# Inverter.net
KiCad netlist of a schematic drawn in Altium Designer
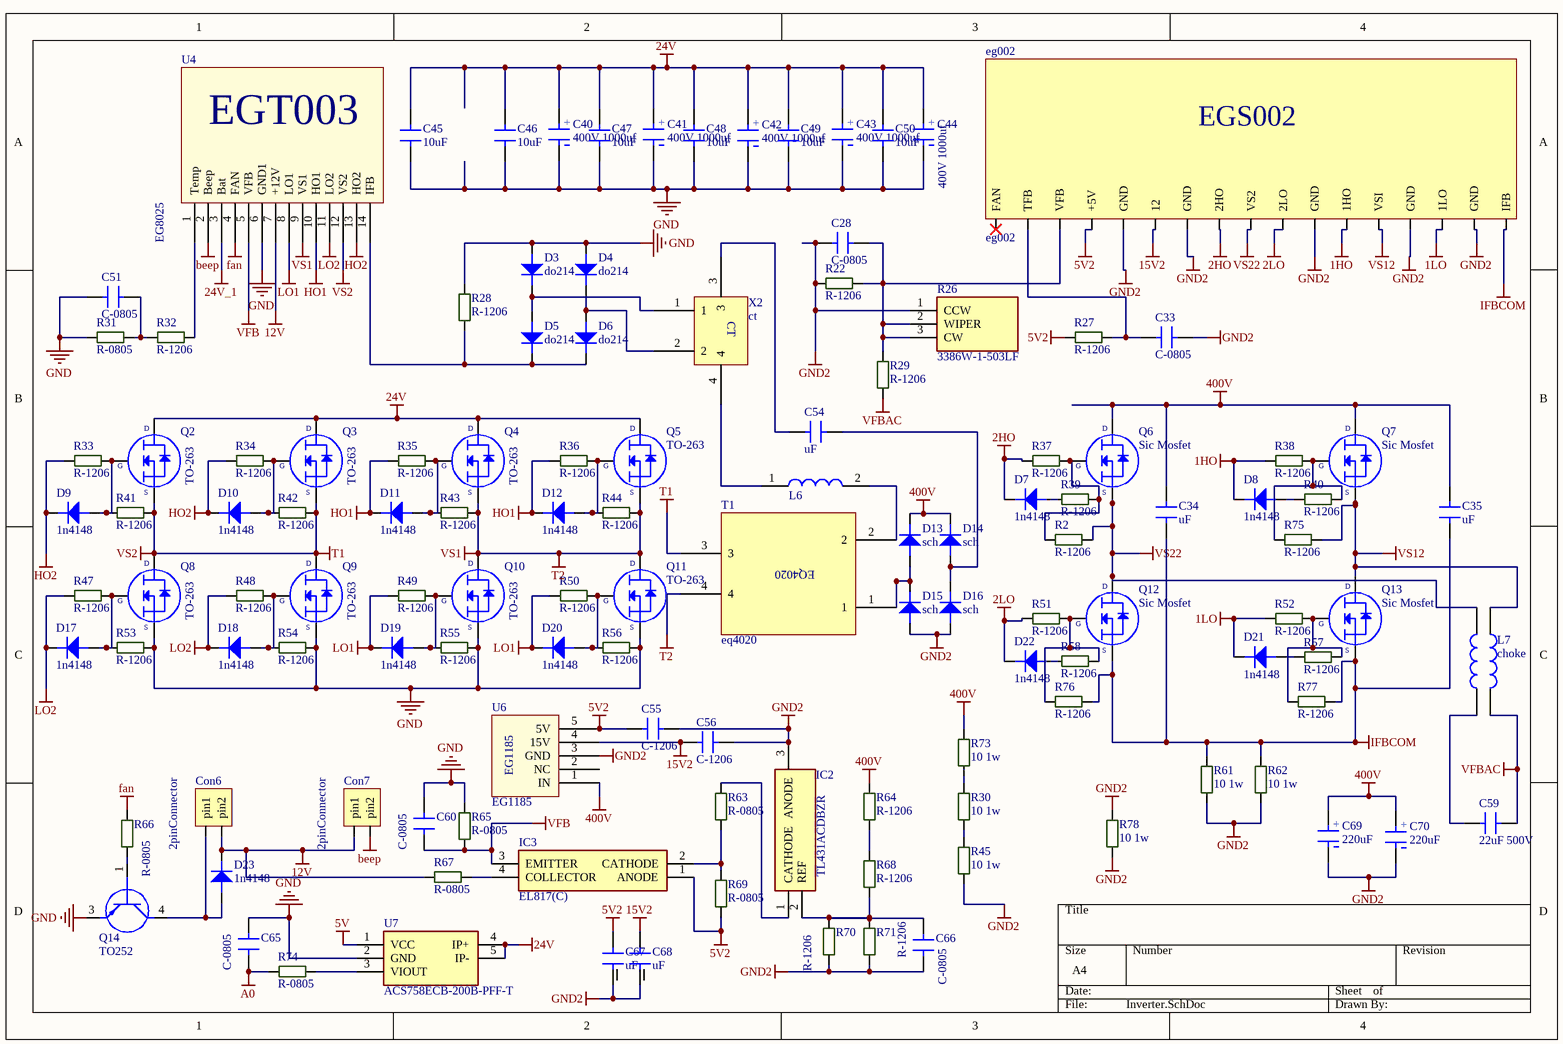
[diagram p0: Inverter.SchDoc]

(export (version "E")
  (design (tool "Eeschema 10.0.6"))
  (components
    (comp (ref "C28") (value "C-0805") (footprint "C-0805W") (libsource (lib "Schlib1") (part "C-0805")))
    (comp (ref "C33") (value "C-0805") (footprint "C-0805W") (libsource (lib "Schlib1") (part "C-0805")))
    (comp (ref "C34") (value "uF") (footprint "680nF bulk") (libsource (lib "Schlib1") (part "680")))
    (comp (ref "C35") (value "uF") (footprint "680nF bulk") (libsource (lib "Schlib1") (part "680")))
    (comp (ref "C40")
      (value "400V 1000uf")
      (footprint "CAP_EEETC1C331V")
      (fields
        (field (name "MANUFACTURER") "Nichicon")
        (field (name "MANUFACTURER PART NUMBER") "LKS1J472MESZ")
        (field (name "TOLERANCE") "20%")
      )
      (libsource (lib "Schlib1") (part "Aluminum Electrolytic Capacitors"))
    )
    (comp (ref "C41")
      (value "400V 1000uf")
      (footprint "CAP_EEETC1C331V")
      (fields
        (field (name "MANUFACTURER") "Nichicon")
        (field (name "MANUFACTURER PART NUMBER") "LKS1J472MESZ")
        (field (name "TOLERANCE") "20%")
      )
      (libsource (lib "Schlib1") (part "Aluminum Electrolytic Capacitors"))
    )
    (comp (ref "C42")
      (value "400V 1000uf")
      (footprint "CAP_EEETC1C331V")
      (fields
        (field (name "MANUFACTURER") "Nichicon")
        (field (name "MANUFACTURER PART NUMBER") "LKS1J472MESZ")
        (field (name "TOLERANCE") "20%")
      )
      (libsource (lib "Schlib1") (part "Aluminum Electrolytic Capacitors"))
    )
    (comp (ref "C43")
      (value "400V 1000uf")
      (footprint "CAP_EEETC1C331V")
      (fields
        (field (name "MANUFACTURER") "Nichicon")
        (field (name "MANUFACTURER PART NUMBER") "LKS1J472MESZ")
        (field (name "TOLERANCE") "20%")
      )
      (libsource (lib "Schlib1") (part "Aluminum Electrolytic Capacitors"))
    )
    (comp (ref "C44")
      (value "400V 1000uf")
      (footprint "CAP_EEETC1C331V")
      (fields
        (field (name "MANUFACTURER") "Nichicon")
        (field (name "MANUFACTURER PART NUMBER") "LKS1J472MESZ")
        (field (name "TOLERANCE") "20%")
      )
      (libsource (lib "Schlib1") (part "Aluminum Electrolytic Capacitors"))
    )
    (comp (ref "C45")
      (value "10uF")
      (footprint "C-2220R")
      (description "2220")
      (fields (field (name "ÖZDISAN PART NUMBER") " CL31B475KBHNNNE") (field (name "MANUFACTURER") "SAMSUNG"))
      (libsource (lib "Schlib1") (part "Cap2220"))
    )
    (comp (ref "C46")
      (value "10uF")
      (footprint "C-2220R")
      (description "2220")
      (fields (field (name "ÖZDISAN PART NUMBER") " CL31B475KBHNNNE") (field (name "MANUFACTURER") "SAMSUNG"))
      (libsource (lib "Schlib1") (part "Cap2220"))
    )
    (comp (ref "C47")
      (value "10uF")
      (footprint "C-2220R")
      (description "2220")
      (fields (field (name "ÖZDISAN PART NUMBER") " CL31B475KBHNNNE") (field (name "MANUFACTURER") "SAMSUNG"))
      (libsource (lib "Schlib1") (part "Cap2220"))
    )
    (comp (ref "C48")
      (value "10uF")
      (footprint "C-2220R")
      (description "2220")
      (fields (field (name "ÖZDISAN PART NUMBER") " CL31B475KBHNNNE") (field (name "MANUFACTURER") "SAMSUNG"))
      (libsource (lib "Schlib1") (part "Cap2220"))
    )
    (comp (ref "C49")
      (value "10uF")
      (footprint "C-2220R")
      (description "2220")
      (fields (field (name "ÖZDISAN PART NUMBER") " CL31B475KBHNNNE") (field (name "MANUFACTURER") "SAMSUNG"))
      (libsource (lib "Schlib1") (part "Cap2220"))
    )
    (comp (ref "C50")
      (value "10uF")
      (footprint "C-2220R")
      (description "2220")
      (fields (field (name "ÖZDISAN PART NUMBER") " CL31B475KBHNNNE") (field (name "MANUFACTURER") "SAMSUNG"))
      (libsource (lib "Schlib1") (part "Cap2220"))
    )
    (comp (ref "C51") (value "C-0805") (footprint "C-0805W") (libsource (lib "Schlib1") (part "C-0805")))
    (comp (ref "C54") (value "uF") (footprint "680nF bulk") (libsource (lib "Schlib1") (part "680")))
    (comp (ref "C55") (value "C-1206") (footprint "C-1206W") (libsource (lib "Schlib1") (part "C-1206")))
    (comp (ref "C56") (value "C-1206") (footprint "C-1206W") (libsource (lib "Schlib1") (part "C-1206")))
    (comp (ref "C59")
      (value "22uF 500V")
      (footprint "CAP.POL 22UF 500VDC - duplicate")
      (libsource (lib "Schlib1") (part "CAP.POL 22UF 500VDC"))
    )
    (comp (ref "C60") (value "C-0805") (footprint "C-0805W") (libsource (lib "Schlib1") (part "C-0805")))
    (comp (ref "C65") (value "C-0805") (footprint "C-0805W") (libsource (lib "Schlib1") (part "C-0805")))
    (comp (ref "C66") (value "C-0805") (footprint "C-0805W") (libsource (lib "Schlib1") (part "C-0805")))
    (comp (ref "C67") (value "uF") (footprint "CapSmdElc") (libsource (lib "Schlib1") (part "CAPSMDELC")))
    (comp (ref "C68") (value "uF") (footprint "CapSmdElc") (libsource (lib "Schlib1") (part "CAPSMDELC")))
    (comp (ref "C69")
      (value "220uF")
      (footprint "Koshin")
      (libsource (lib "Schlib1") (part "CAP.EL.220uF 500V"))
    )
    (comp (ref "C70")
      (value "220uF")
      (footprint "Koshin")
      (libsource (lib "Schlib1") (part "CAP.EL.220uF 500V"))
    )
    (comp (ref "Con6")
      (value "2pinConnector")
      (footprint "2pinCon")
      (libsource (lib "Schlib1") (part "2pinConnector"))
    )
    (comp (ref "Con7")
      (value "2pinConnector")
      (footprint "2pinCon")
      (libsource (lib "Schlib1") (part "2pinConnector"))
    )
    (comp (ref "D3")
      (value "do214")
      (footprint "DO-214AC")
      (description "DIODE FAST SWITCHING Single 150mA 75V SMT SOD323")
      (libsource (lib "Schlib1") (part "do214"))
    )
    (comp (ref "D4")
      (value "do214")
      (footprint "DO-214AC")
      (description "DIODE FAST SWITCHING Single 150mA 75V SMT SOD323")
      (libsource (lib "Schlib1") (part "do214"))
    )
    (comp (ref "D5")
      (value "do214")
      (footprint "DO-214AC")
      (description "DIODE FAST SWITCHING Single 150mA 75V SMT SOD323")
      (libsource (lib "Schlib1") (part "do214"))
    )
    (comp (ref "D6")
      (value "do214")
      (footprint "DO-214AC")
      (description "DIODE FAST SWITCHING Single 150mA 75V SMT SOD323")
      (libsource (lib "Schlib1") (part "do214"))
    )
    (comp (ref "D7")
      (value "1n4148")
      (footprint "SOD123")
      (description "Diode Small Signal Switching 100V 0.15A 2-Pin SOD-123 T/R")
      (fields
        (field (name "MANUFACTURER") "Vishay")
        (field (name "MANUFACTURER PART NUMBER") "1N4148W-E3-18")
      )
      (libsource (lib "Schlib1") (part "1N4148W-E3-18"))
    )
    (comp (ref "D8")
      (value "1n4148")
      (footprint "SOD123")
      (description "Diode Small Signal Switching 100V 0.15A 2-Pin SOD-123 T/R")
      (fields
        (field (name "MANUFACTURER") "Vishay")
        (field (name "MANUFACTURER PART NUMBER") "1N4148W-E3-18")
      )
      (libsource (lib "Schlib1") (part "1N4148W-E3-18"))
    )
    (comp (ref "D9")
      (value "1n4148")
      (footprint "SOD123")
      (description "Diode Small Signal Switching 100V 0.15A 2-Pin SOD-123 T/R")
      (fields
        (field (name "MANUFACTURER") "Vishay")
        (field (name "MANUFACTURER PART NUMBER") "1N4148W-E3-18")
      )
      (libsource (lib "Schlib1") (part "1N4148W-E3-18"))
    )
    (comp (ref "D10")
      (value "1n4148")
      (footprint "SOD123")
      (description "Diode Small Signal Switching 100V 0.15A 2-Pin SOD-123 T/R")
      (fields
        (field (name "MANUFACTURER") "Vishay")
        (field (name "MANUFACTURER PART NUMBER") "1N4148W-E3-18")
      )
      (libsource (lib "Schlib1") (part "1N4148W-E3-18"))
    )
    (comp (ref "D11")
      (value "1n4148")
      (footprint "SOD123")
      (description "Diode Small Signal Switching 100V 0.15A 2-Pin SOD-123 T/R")
      (fields
        (field (name "MANUFACTURER") "Vishay")
        (field (name "MANUFACTURER PART NUMBER") "1N4148W-E3-18")
      )
      (libsource (lib "Schlib1") (part "1N4148W-E3-18"))
    )
    (comp (ref "D12")
      (value "1n4148")
      (footprint "SOD123")
      (description "Diode Small Signal Switching 100V 0.15A 2-Pin SOD-123 T/R")
      (fields
        (field (name "MANUFACTURER") "Vishay")
        (field (name "MANUFACTURER PART NUMBER") "1N4148W-E3-18")
      )
      (libsource (lib "Schlib1") (part "1N4148W-E3-18"))
    )
    (comp (ref "D13")
      (value "sch")
      (footprint "DPAK_TO263 - sch")
      (description "DIODE FAST SWITCHING Single 150mA 75V SMT SOD323")
      (libsource (lib "Schlib1") (part "sch"))
    )
    (comp (ref "D14")
      (value "sch")
      (footprint "DPAK_TO263 - sch")
      (description "DIODE FAST SWITCHING Single 150mA 75V SMT SOD323")
      (libsource (lib "Schlib1") (part "sch"))
    )
    (comp (ref "D15")
      (value "sch")
      (footprint "DPAK_TO263 - sch")
      (description "DIODE FAST SWITCHING Single 150mA 75V SMT SOD323")
      (libsource (lib "Schlib1") (part "sch"))
    )
    (comp (ref "D16")
      (value "sch")
      (footprint "DPAK_TO263 - sch")
      (description "DIODE FAST SWITCHING Single 150mA 75V SMT SOD323")
      (libsource (lib "Schlib1") (part "sch"))
    )
    (comp (ref "D17")
      (value "1n4148")
      (footprint "SOD123")
      (description "Diode Small Signal Switching 100V 0.15A 2-Pin SOD-123 T/R")
      (fields
        (field (name "MANUFACTURER") "Vishay")
        (field (name "MANUFACTURER PART NUMBER") "1N4148W-E3-18")
      )
      (libsource (lib "Schlib1") (part "1N4148W-E3-18"))
    )
    (comp (ref "D18")
      (value "1n4148")
      (footprint "SOD123")
      (description "Diode Small Signal Switching 100V 0.15A 2-Pin SOD-123 T/R")
      (fields
        (field (name "MANUFACTURER") "Vishay")
        (field (name "MANUFACTURER PART NUMBER") "1N4148W-E3-18")
      )
      (libsource (lib "Schlib1") (part "1N4148W-E3-18"))
    )
    (comp (ref "D19")
      (value "1n4148")
      (footprint "SOD123")
      (description "Diode Small Signal Switching 100V 0.15A 2-Pin SOD-123 T/R")
      (fields
        (field (name "MANUFACTURER") "Vishay")
        (field (name "MANUFACTURER PART NUMBER") "1N4148W-E3-18")
      )
      (libsource (lib "Schlib1") (part "1N4148W-E3-18"))
    )
    (comp (ref "D20")
      (value "1n4148")
      (footprint "SOD123")
      (description "Diode Small Signal Switching 100V 0.15A 2-Pin SOD-123 T/R")
      (fields
        (field (name "MANUFACTURER") "Vishay")
        (field (name "MANUFACTURER PART NUMBER") "1N4148W-E3-18")
      )
      (libsource (lib "Schlib1") (part "1N4148W-E3-18"))
    )
    (comp (ref "D21")
      (value "1n4148")
      (footprint "SOD123")
      (description "Diode Small Signal Switching 100V 0.15A 2-Pin SOD-123 T/R")
      (fields
        (field (name "MANUFACTURER") "Vishay")
        (field (name "MANUFACTURER PART NUMBER") "1N4148W-E3-18")
      )
      (libsource (lib "Schlib1") (part "1N4148W-E3-18"))
    )
    (comp (ref "D22")
      (value "1n4148")
      (footprint "SOD123")
      (description "Diode Small Signal Switching 100V 0.15A 2-Pin SOD-123 T/R")
      (fields
        (field (name "MANUFACTURER") "Vishay")
        (field (name "MANUFACTURER PART NUMBER") "1N4148W-E3-18")
      )
      (libsource (lib "Schlib1") (part "1N4148W-E3-18"))
    )
    (comp (ref "D23")
      (value "1n4148")
      (footprint "SOD123")
      (description "Diode Small Signal Switching 100V 0.15A 2-Pin SOD-123 T/R")
      (fields
        (field (name "MANUFACTURER") "Vishay")
        (field (name "MANUFACTURER PART NUMBER") "1N4148W-E3-18")
      )
      (libsource (lib "Schlib1") (part "1N4148W-E3-18"))
    )
    (comp (ref "eg002") (value "eg002") (footprint "eg002") (libsource (lib "Schlib1") (part "eg002")))
    (comp (ref "IC2")
      (value "TL431ACDBZR")
      (footprint "SamacSys:SOT95P237X112-3N")
      (description "Integrated Circuit")
      (fields (field (name "MOUSER PART NUMBER") "595-TL431ACDBZR"))
      (libsource (lib "*") (part "TL431ACDBZR"))
    )
    (comp (ref "IC3")
      (value "EL817(C)")
      (footprint "DIP762W60P254L458H480Q4N")
      (description "Integrated Circuit")
      (fields (field (name "MOUSER PART NUMBER") "638-EL817C"))
      (libsource (lib "Schlib1") (part "EL817(C)"))
    )
    (comp (ref "L6")
      (value "inducter_SMPI06050")
      (footprint "inductor")
      (libsource (lib "Schlib1") (part "inducter_SMPI06050"))
    )
    (comp (ref "L7") (value "choke") (footprint "choke") (libsource (lib "Schlib1") (part "choke")))
    (comp (ref "Q2") (value "TO-263") (footprint "DPAK_TO263") (libsource (lib "Schlib1") (part "TO-263_1")))
    (comp (ref "Q3") (value "TO-263") (footprint "DPAK_TO263") (libsource (lib "Schlib1") (part "TO-263_1")))
    (comp (ref "Q4") (value "TO-263") (footprint "DPAK_TO263") (libsource (lib "Schlib1") (part "TO-263_1")))
    (comp (ref "Q5") (value "TO-263") (footprint "DPAK_TO263") (libsource (lib "Schlib1") (part "TO-263_1")))
    (comp (ref "Q6")
      (value "Sic Mosfet")
      (footprint "247")
      (description "SiC Mosfet To247")
      (libsource (lib "Schlib1") (part "Sic Mosfet To247"))
    )
    (comp (ref "Q7")
      (value "Sic Mosfet")
      (footprint "247")
      (description "SiC Mosfet To247")
      (libsource (lib "Schlib1") (part "Sic Mosfet To247"))
    )
    (comp (ref "Q8") (value "TO-263") (footprint "DPAK_TO263") (libsource (lib "Schlib1") (part "TO-263_1")))
    (comp (ref "Q9") (value "TO-263") (footprint "DPAK_TO263") (libsource (lib "Schlib1") (part "TO-263_1")))
    (comp (ref "Q10") (value "TO-263") (footprint "DPAK_TO263") (libsource (lib "Schlib1") (part "TO-263_1")))
    (comp (ref "Q11") (value "TO-263") (footprint "DPAK_TO263") (libsource (lib "Schlib1") (part "TO-263_1")))
    (comp (ref "Q12")
      (value "Sic Mosfet")
      (footprint "247")
      (description "SiC Mosfet To247")
      (libsource (lib "Schlib1") (part "Sic Mosfet To247"))
    )
    (comp (ref "Q13")
      (value "Sic Mosfet")
      (footprint "247")
      (description "SiC Mosfet To247")
      (libsource (lib "Schlib1") (part "Sic Mosfet To247"))
    )
    (comp (ref "Q14") (value "TO252") (footprint "D-PAK_TO252AA") (libsource (lib "Schlib1") (part "TO252")))
    (comp (ref "R2") (value "R-1206") (footprint "R-1206W") (libsource (lib "Schlib1") (part "R-1206")))
    (comp (ref "R22") (value "R-1206") (footprint "R-1206W") (libsource (lib "Schlib1") (part "R-1206")))
    (comp (ref "R26")
      (value "3386W-1-503LF")
      (footprint "SamacSys:3386W")
      (description "Resistor")
      (fields (field (name "MOUSER PART NUMBER") "652-3386W-1-503LF"))
      (libsource (lib "*") (part "3386W-1-503LF"))
    )
    (comp (ref "R27") (value "R-1206") (footprint "R-1206W") (libsource (lib "Schlib1") (part "R-1206")))
    (comp (ref "R28") (value "R-1206") (footprint "R-1206W") (libsource (lib "Schlib1") (part "R-1206")))
    (comp (ref "R29") (value "R-1206") (footprint "R-1206W") (libsource (lib "Schlib1") (part "R-1206")))
    (comp (ref "R30") (value "10 1w") (footprint "R-2512W") (libsource (lib "Schlib1") (part "R-2512")))
    (comp (ref "R31") (value "R-0805") (footprint "R-0805W") (libsource (lib "Schlib1") (part "R-0805")))
    (comp (ref "R32") (value "R-1206") (footprint "R-1206W") (libsource (lib "Schlib1") (part "R-1206")))
    (comp (ref "R33") (value "R-1206") (footprint "R-1206W") (libsource (lib "Schlib1") (part "R-1206")))
    (comp (ref "R34") (value "R-1206") (footprint "R-1206W") (libsource (lib "Schlib1") (part "R-1206")))
    (comp (ref "R35") (value "R-1206") (footprint "R-1206W") (libsource (lib "Schlib1") (part "R-1206")))
    (comp (ref "R36") (value "R-1206") (footprint "R-1206W") (libsource (lib "Schlib1") (part "R-1206")))
    (comp (ref "R37") (value "R-1206") (footprint "R-1206W") (libsource (lib "Schlib1") (part "R-1206")))
    (comp (ref "R38") (value "R-1206") (footprint "R-1206W") (libsource (lib "Schlib1") (part "R-1206")))
    (comp (ref "R39") (value "R-1206") (footprint "R-1206W") (libsource (lib "Schlib1") (part "R-1206")))
    (comp (ref "R40") (value "R-1206") (footprint "R-1206W") (libsource (lib "Schlib1") (part "R-1206")))
    (comp (ref "R41") (value "R-1206") (footprint "R-1206W") (libsource (lib "Schlib1") (part "R-1206")))
    (comp (ref "R42") (value "R-1206") (footprint "R-1206W") (libsource (lib "Schlib1") (part "R-1206")))
    (comp (ref "R43") (value "R-1206") (footprint "R-1206W") (libsource (lib "Schlib1") (part "R-1206")))
    (comp (ref "R44") (value "R-1206") (footprint "R-1206W") (libsource (lib "Schlib1") (part "R-1206")))
    (comp (ref "R45") (value "10 1w") (footprint "R-2512W") (libsource (lib "Schlib1") (part "R-2512")))
    (comp (ref "R47") (value "R-1206") (footprint "R-1206W") (libsource (lib "Schlib1") (part "R-1206")))
    (comp (ref "R48") (value "R-1206") (footprint "R-1206W") (libsource (lib "Schlib1") (part "R-1206")))
    (comp (ref "R49") (value "R-1206") (footprint "R-1206W") (libsource (lib "Schlib1") (part "R-1206")))
    (comp (ref "R50") (value "R-1206") (footprint "R-1206W") (libsource (lib "Schlib1") (part "R-1206")))
    (comp (ref "R51") (value "R-1206") (footprint "R-1206W") (libsource (lib "Schlib1") (part "R-1206")))
    (comp (ref "R52") (value "R-1206") (footprint "R-1206W") (libsource (lib "Schlib1") (part "R-1206")))
    (comp (ref "R53") (value "R-1206") (footprint "R-1206W") (libsource (lib "Schlib1") (part "R-1206")))
    (comp (ref "R54") (value "R-1206") (footprint "R-1206W") (libsource (lib "Schlib1") (part "R-1206")))
    (comp (ref "R55") (value "R-1206") (footprint "R-1206W") (libsource (lib "Schlib1") (part "R-1206")))
    (comp (ref "R56") (value "R-1206") (footprint "R-1206W") (libsource (lib "Schlib1") (part "R-1206")))
    (comp (ref "R57") (value "R-1206") (footprint "R-1206W") (libsource (lib "Schlib1") (part "R-1206")))
    (comp (ref "R58") (value "R-1206") (footprint "R-1206W") (libsource (lib "Schlib1") (part "R-1206")))
    (comp (ref "R61") (value "10 1w") (footprint "R-2512W") (libsource (lib "Schlib1") (part "R-2512")))
    (comp (ref "R62") (value "10 1w") (footprint "R-2512W") (libsource (lib "Schlib1") (part "R-2512")))
    (comp (ref "R63") (value "R-0805") (footprint "R-0805W") (libsource (lib "Schlib1") (part "R-0805")))
    (comp (ref "R64") (value "R-1206") (footprint "R-1206W") (libsource (lib "Schlib1") (part "R-1206")))
    (comp (ref "R65") (value "R-0805") (footprint "R-0805W") (libsource (lib "Schlib1") (part "R-0805")))
    (comp (ref "R66") (value "R-0805") (footprint "R-0805W") (libsource (lib "Schlib1") (part "R-0805")))
    (comp (ref "R67") (value "R-0805") (footprint "R-0805W") (libsource (lib "Schlib1") (part "R-0805")))
    (comp (ref "R68") (value "R-1206") (footprint "R-1206W") (libsource (lib "Schlib1") (part "R-1206")))
    (comp (ref "R69") (value "R-0805") (footprint "R-0805W") (libsource (lib "Schlib1") (part "R-0805")))
    (comp (ref "R70") (value "R-1206") (footprint "R-1206W") (libsource (lib "Schlib1") (part "R-1206")))
    (comp (ref "R71") (value "R-1206") (footprint "R-1206W") (libsource (lib "Schlib1") (part "R-1206")))
    (comp (ref "R73") (value "10 1w") (footprint "R-2512W") (libsource (lib "Schlib1") (part "R-2512")))
    (comp (ref "R74") (value "R-0805") (footprint "R-0805W") (libsource (lib "Schlib1") (part "R-0805")))
    (comp (ref "R75") (value "R-1206") (footprint "R-1206W") (libsource (lib "Schlib1") (part "R-1206")))
    (comp (ref "R76") (value "R-1206") (footprint "R-1206W") (libsource (lib "Schlib1") (part "R-1206")))
    (comp (ref "R77") (value "R-1206") (footprint "R-1206W") (libsource (lib "Schlib1") (part "R-1206")))
    (comp (ref "R78") (value "10 1w") (footprint "R-2512W") (libsource (lib "Schlib1") (part "R-2512")))
    (comp (ref "T1") (value "eq4020") (footprint "eq4020") (libsource (lib "Schlib1") (part "eq4020")))
    (comp (ref "U4") (value "EG8025") (footprint "EGT003") (libsource (lib "Schlib1") (part "EGT003")))
    (comp (ref "U6") (value "EG1185") (footprint "EG1185") (libsource (lib "Schlib1") (part "eg1185")))
    (comp (ref "U7")
      (value "ACS758ECB-200B-PFF-T")
      (footprint "ACS756SCA-050B-PFF-T_2")
      (description "Undefined or Miscellaneous")
      (libsource (lib "Schlib1") (part "ACS758ECB-200B-PFF-T"))
    )
    (comp (ref "X2") (value "ct") (footprint "ct") (libsource (lib "Schlib1") (part "ct")))
  )
  (nets
    (net (code "1") (name "1HO") (class "Default")
      (node (ref "D8") (pin "k") (pinfunction "k_k") (pintype "passive"))
      (node (ref "R38") (pin "1") (pinfunction "1_1") (pintype "passive"))
      (node (ref "eg002") (pin "6") (pinfunction "1HO_6") (pintype "passive"))
    )
    (net (code "2") (name "1LO") (class "Default")
      (node (ref "D21") (pin "k") (pinfunction "k_k") (pintype "passive"))
      (node (ref "R52") (pin "1") (pinfunction "1_1") (pintype "passive"))
      (node (ref "eg002") (pin "3") (pinfunction "1LO_3") (pintype "passive"))
    )
    (net (code "3") (name "2HO") (class "Default")
      (node (ref "D7") (pin "k") (pinfunction "k_k") (pintype "passive"))
      (node (ref "R37") (pin "1") (pinfunction "1_1") (pintype "passive"))
      (node (ref "eg002") (pin "10") (pinfunction "2HO_10") (pintype "passive"))
    )
    (net (code "4") (name "2LO") (class "Default")
      (node (ref "D22") (pin "k") (pinfunction "k_k") (pintype "passive"))
      (node (ref "R51") (pin "1") (pinfunction "1_1") (pintype "passive"))
      (node (ref "eg002") (pin "8") (pinfunction "2LO_8") (pintype "passive"))
    )
    (net (code "5") (name "5V") (class "Default")
      (node (ref "U7") (pin "1") (pinfunction "VCC_1") (pintype "passive"))
    )
    (net (code "6") (name "5V2") (class "Default")
      (node (ref "C55") (pin "1") (pinfunction "1_1") (pintype "passive"))
      (node (ref "C67") (pin "1") (pinfunction "1_1") (pintype "passive"))
      (node (ref "IC3") (pin "1") (pinfunction "ANODE_1") (pintype "passive"))
      (node (ref "R27") (pin "1") (pinfunction "1_1") (pintype "passive"))
      (node (ref "R69") (pin "1") (pinfunction "1_1") (pintype "passive"))
      (node (ref "U6") (pin "5") (pinfunction "5V_5") (pintype "passive"))
      (node (ref "eg002") (pin "14") (pinfunction "+5V_14") (pintype "passive"))
    )
    (net (code "7") (name "12V") (class "Default")
      (node (ref "Con6") (pin "2") (pinfunction "pin2_2") (pintype "passive"))
      (node (ref "Con7") (pin "1") (pinfunction "pin1_1") (pintype "passive"))
      (node (ref "D23") (pin "k") (pinfunction "k_k") (pintype "passive"))
      (node (ref "R67") (pin "1") (pinfunction "1_1") (pintype "passive"))
      (node (ref "U4") (pin "7") (pinfunction "+12V_7") (pintype "passive"))
    )
    (net (code "8") (name "15V2") (class "Default")
      (node (ref "C56") (pin "1") (pinfunction "1_1") (pintype "passive"))
      (node (ref "C68") (pin "1") (pinfunction "1_1") (pintype "passive"))
      (node (ref "U6") (pin "4") (pinfunction "15V_4") (pintype "passive"))
      (node (ref "eg002") (pin "12") (pinfunction "12_12") (pintype "passive"))
    )
    (net (code "9") (name "24V") (class "Default")
      (node (ref "C40") (pin "1") (pinfunction "1_1") (pintype "passive"))
      (node (ref "C41") (pin "1") (pinfunction "1_1") (pintype "passive"))
      (node (ref "C42") (pin "1") (pinfunction "1_1") (pintype "passive"))
      (node (ref "C43") (pin "1") (pinfunction "1_1") (pintype "passive"))
      (node (ref "C44") (pin "1") (pinfunction "1_1") (pintype "passive"))
      (node (ref "C45") (pin "1") (pinfunction "1_1") (pintype "passive"))
      (node (ref "C46") (pin "1") (pinfunction "1_1") (pintype "passive"))
      (node (ref "C47") (pin "1") (pinfunction "1_1") (pintype "passive"))
      (node (ref "C48") (pin "1") (pinfunction "1_1") (pintype "passive"))
      (node (ref "C49") (pin "1") (pinfunction "1_1") (pintype "passive"))
      (node (ref "C50") (pin "1") (pinfunction "1_1") (pintype "passive"))
      (node (ref "Q2") (pin "3") (pinfunction "3_3") (pintype "passive"))
      (node (ref "Q3") (pin "3") (pinfunction "3_3") (pintype "passive"))
      (node (ref "Q4") (pin "3") (pinfunction "3_3") (pintype "passive"))
      (node (ref "Q5") (pin "3") (pinfunction "3_3") (pintype "passive"))
      (node (ref "U7") (pin "4") (pinfunction "IP+_4") (pintype "passive"))
      (node (ref "U7") (pin "5") (pinfunction "IP-_5") (pintype "passive"))
    )
    (net (code "10") (name "24V_1") (class "Default")
      (node (ref "U4") (pin "3") (pinfunction "Bat_3") (pintype "passive"))
    )
    (net (code "11") (name "400V") (class "Default")
      (node (ref "C34") (pin "2") (pinfunction "2_2") (pintype "passive"))
      (node (ref "C35") (pin "2") (pinfunction "2_2") (pintype "passive"))
      (node (ref "C69") (pin "2") (pinfunction "2_2") (pintype "passive"))
      (node (ref "C70") (pin "2") (pinfunction "2_2") (pintype "passive"))
      (node (ref "D13") (pin "2") (pinfunction "2_2") (pintype "passive"))
      (node (ref "D14") (pin "2") (pinfunction "2_2") (pintype "passive"))
      (node (ref "Q6") (pin "2") (pinfunction "2_2") (pintype "passive"))
      (node (ref "Q7") (pin "2") (pinfunction "2_2") (pintype "passive"))
      (node (ref "R64") (pin "2") (pinfunction "2_2") (pintype "passive"))
      (node (ref "R73") (pin "2") (pinfunction "2_2") (pintype "passive"))
      (node (ref "U6") (pin "1") (pinfunction "IN_1") (pintype "passive"))
    )
    (net (code "12") (name "A0") (class "Default")
      (node (ref "C65") (pin "1") (pinfunction "1_1") (pintype "passive"))
      (node (ref "R74") (pin "2") (pinfunction "2_2") (pintype "passive"))
    )
    (net (code "13") (name "GND") (class "Default")
      (node (ref "C40") (pin "2") (pinfunction "2_2") (pintype "passive"))
      (node (ref "C41") (pin "2") (pinfunction "2_2") (pintype "passive"))
      (node (ref "C42") (pin "2") (pinfunction "2_2") (pintype "passive"))
      (node (ref "C43") (pin "2") (pinfunction "2_2") (pintype "passive"))
      (node (ref "C44") (pin "2") (pinfunction "2_2") (pintype "passive"))
      (node (ref "C45") (pin "2") (pinfunction "2_2") (pintype "passive"))
      (node (ref "C46") (pin "2") (pinfunction "2_2") (pintype "passive"))
      (node (ref "C47") (pin "2") (pinfunction "2_2") (pintype "passive"))
      (node (ref "C48") (pin "2") (pinfunction "2_2") (pintype "passive"))
      (node (ref "C49") (pin "2") (pinfunction "2_2") (pintype "passive"))
      (node (ref "C50") (pin "2") (pinfunction "2_2") (pintype "passive"))
      (node (ref "C51") (pin "1") (pinfunction "1_1") (pintype "passive"))
      (node (ref "C60") (pin "2") (pinfunction "2_2") (pintype "passive"))
      (node (ref "C65") (pin "2") (pinfunction "2_2") (pintype "passive"))
      (node (ref "D3") (pin "a") (pinfunction "a_a") (pintype "passive"))
      (node (ref "D4") (pin "a") (pinfunction "a_a") (pintype "passive"))
      (node (ref "Q10") (pin "2") (pinfunction "2_2") (pintype "passive"))
      (node (ref "Q11") (pin "2") (pinfunction "2_2") (pintype "passive"))
      (node (ref "Q14") (pin "3") (pinfunction "E_3") (pintype "passive"))
      (node (ref "Q8") (pin "2") (pinfunction "2_2") (pintype "passive"))
      (node (ref "Q9") (pin "2") (pinfunction "2_2") (pintype "passive"))
      (node (ref "R28") (pin "2") (pinfunction "2_2") (pintype "passive"))
      (node (ref "R31") (pin "1") (pinfunction "1_1") (pintype "passive"))
      (node (ref "R53") (pin "2") (pinfunction "2_2") (pintype "passive"))
      (node (ref "R54") (pin "2") (pinfunction "2_2") (pintype "passive"))
      (node (ref "R55") (pin "2") (pinfunction "2_2") (pintype "passive"))
      (node (ref "R56") (pin "2") (pinfunction "2_2") (pintype "passive"))
      (node (ref "R65") (pin "2") (pinfunction "2_2") (pintype "passive"))
      (node (ref "U4") (pin "6") (pinfunction "GND1_6") (pintype "passive"))
      (node (ref "U7") (pin "2") (pinfunction "GND_2") (pintype "passive"))
    )
    (net (code "14") (name "GND2") (class "Default")
      (node (ref "C28") (pin "1") (pinfunction "1_1") (pintype "passive"))
      (node (ref "C33") (pin "2") (pinfunction "2_2") (pintype "passive"))
      (node (ref "C55") (pin "2") (pinfunction "2_2") (pintype "passive"))
      (node (ref "C56") (pin "2") (pinfunction "2_2") (pintype "passive"))
      (node (ref "C66") (pin "1") (pinfunction "1_1") (pintype "passive"))
      (node (ref "C67") (pin "2") (pinfunction "2_2") (pintype "passive"))
      (node (ref "C68") (pin "2") (pinfunction "2_2") (pintype "passive"))
      (node (ref "C69") (pin "1") (pinfunction "1_1") (pintype "passive"))
      (node (ref "C70") (pin "1") (pinfunction "1_1") (pintype "passive"))
      (node (ref "D15") (pin "1") (pinfunction "1_1") (pintype "passive"))
      (node (ref "D16") (pin "1") (pinfunction "1_1") (pintype "passive"))
      (node (ref "IC2") (pin "3") (pinfunction "ANODE_3") (pintype "passive"))
      (node (ref "R22") (pin "2") (pinfunction "2_2") (pintype "passive"))
      (node (ref "R26") (pin "1") (pinfunction "CCW_1") (pintype "passive"))
      (node (ref "R45") (pin "1") (pinfunction "1_1") (pintype "passive"))
      (node (ref "R61") (pin "1") (pinfunction "1_1") (pintype "passive"))
      (node (ref "R62") (pin "1") (pinfunction "1_1") (pintype "passive"))
      (node (ref "R70") (pin "1") (pinfunction "1_1") (pintype "passive"))
      (node (ref "R71") (pin "1") (pinfunction "1_1") (pintype "passive"))
      (node (ref "R78") (pin "1") (pinfunction "1_1") (pintype "passive"))
      (node (ref "R78") (pin "2") (pinfunction "2_2") (pintype "passive"))
      (node (ref "U6") (pin "3") (pinfunction "GND_3") (pintype "passive"))
      (node (ref "eg002") (pin "11") (pinfunction "GND_11") (pintype "passive"))
      (node (ref "eg002") (pin "13") (pinfunction "GND_13") (pintype "passive"))
      (node (ref "eg002") (pin "2") (pinfunction "GND_2") (pintype "passive"))
      (node (ref "eg002") (pin "4") (pinfunction "GND_4") (pintype "passive"))
      (node (ref "eg002") (pin "7") (pinfunction "GND_7") (pintype "passive"))
    )
    (net (code "15") (name "HO1") (class "Default")
      (node (ref "D11") (pin "k") (pinfunction "k_k") (pintype "passive"))
      (node (ref "D12") (pin "k") (pinfunction "k_k") (pintype "passive"))
      (node (ref "R35") (pin "1") (pinfunction "1_1") (pintype "passive"))
      (node (ref "R36") (pin "1") (pinfunction "1_1") (pintype "passive"))
      (node (ref "U4") (pin "10") (pinfunction "HO1_10") (pintype "passive"))
    )
    (net (code "16") (name "HO2") (class "Default")
      (node (ref "D10") (pin "k") (pinfunction "k_k") (pintype "passive"))
      (node (ref "D9") (pin "k") (pinfunction "k_k") (pintype "passive"))
      (node (ref "R33") (pin "1") (pinfunction "1_1") (pintype "passive"))
      (node (ref "R34") (pin "1") (pinfunction "1_1") (pintype "passive"))
      (node (ref "U4") (pin "13") (pinfunction "HO2_13") (pintype "passive"))
    )
    (net (code "17") (name "IFBCOM") (class "Default")
      (node (ref "C34") (pin "1") (pinfunction "1_1") (pintype "passive"))
      (node (ref "C35") (pin "1") (pinfunction "1_1") (pintype "passive"))
      (node (ref "Q12") (pin "3") (pinfunction "3_3") (pintype "passive"))
      (node (ref "Q13") (pin "3") (pinfunction "3_3") (pintype "passive"))
      (node (ref "R61") (pin "2") (pinfunction "2_2") (pintype "passive"))
      (node (ref "R62") (pin "2") (pinfunction "2_2") (pintype "passive"))
      (node (ref "R76") (pin "1") (pinfunction "1_1") (pintype "passive"))
      (node (ref "R77") (pin "1") (pinfunction "1_1") (pintype "passive"))
      (node (ref "eg002") (pin "1") (pinfunction "IFB_1") (pintype "passive"))
    )
    (net (code "18") (name "LO1") (class "Default")
      (node (ref "D19") (pin "k") (pinfunction "k_k") (pintype "passive"))
      (node (ref "D20") (pin "k") (pinfunction "k_k") (pintype "passive"))
      (node (ref "R49") (pin "1") (pinfunction "1_1") (pintype "passive"))
      (node (ref "R50") (pin "1") (pinfunction "1_1") (pintype "passive"))
      (node (ref "U4") (pin "8") (pinfunction "LO1_8") (pintype "passive"))
    )
    (net (code "19") (name "LO2") (class "Default")
      (node (ref "D17") (pin "k") (pinfunction "k_k") (pintype "passive"))
      (node (ref "D18") (pin "k") (pinfunction "k_k") (pintype "passive"))
      (node (ref "R47") (pin "1") (pinfunction "1_1") (pintype "passive"))
      (node (ref "R48") (pin "1") (pinfunction "1_1") (pintype "passive"))
      (node (ref "U4") (pin "11") (pinfunction "LO2_11") (pintype "passive"))
    )
    (net (code "20") (name "Net-(C51-Pad2)") (class "Default")
      (node (ref "C51") (pin "2") (pinfunction "2_2") (pintype "passive"))
      (node (ref "R31") (pin "2") (pinfunction "2_2") (pintype "passive"))
      (node (ref "R32") (pin "1") (pinfunction "1_1") (pintype "passive"))
    )
    (net (code "21") (name "Net-(C54-Pad1)") (class "Default")
      (node (ref "C54") (pin "1") (pinfunction "1_1") (pintype "passive"))
      (node (ref "X2") (pin "3") (pinfunction "3_3") (pintype "passive"))
    )
    (net (code "22") (name "Net-(C54-Pad2)") (class "Default")
      (node (ref "C54") (pin "2") (pinfunction "2_2") (pintype "passive"))
      (node (ref "D14") (pin "1") (pinfunction "1_1") (pintype "passive"))
      (node (ref "D16") (pin "2") (pinfunction "2_2") (pintype "passive"))
    )
    (net (code "23") (name "Net-(C59-Pad1)") (class "Default")
      (node (ref "C59") (pin "1") (pinfunction "1_1") (pintype "passive"))
      (node (ref "L7") (pin "4") (pinfunction "4_4") (pintype "passive"))
    )
    (net (code "24") (name "Net-(Con6-pin1)") (class "Default")
      (node (ref "Con6") (pin "1") (pinfunction "pin1_1") (pintype "passive"))
      (node (ref "D23") (pin "a") (pinfunction "a_a") (pintype "passive"))
      (node (ref "Q14") (pin "4") (pinfunction "C_4") (pintype "passive"))
    )
    (net (code "25") (name "Net-(D3-Padk)") (class "Default")
      (node (ref "D3") (pin "k") (pinfunction "k_k") (pintype "passive"))
      (node (ref "D5") (pin "a") (pinfunction "a_a") (pintype "passive"))
      (node (ref "X2") (pin "1") (pinfunction "1_1") (pintype "passive"))
    )
    (net (code "26") (name "Net-(D4-Padk)") (class "Default")
      (node (ref "D4") (pin "k") (pinfunction "k_k") (pintype "passive"))
      (node (ref "D6") (pin "a") (pinfunction "a_a") (pintype "passive"))
      (node (ref "X2") (pin "2") (pinfunction "2_2") (pintype "passive"))
    )
    (net (code "27") (name "Net-(D7-Pada)") (class "Default")
      (node (ref "D7") (pin "a") (pinfunction "a_a") (pintype "passive"))
      (node (ref "R39") (pin "1") (pinfunction "1_1") (pintype "passive"))
    )
    (net (code "28") (name "Net-(D8-Pada)") (class "Default")
      (node (ref "D8") (pin "a") (pinfunction "a_a") (pintype "passive"))
      (node (ref "R40") (pin "1") (pinfunction "1_1") (pintype "passive"))
    )
    (net (code "29") (name "Net-(D9-Pada)") (class "Default")
      (node (ref "D9") (pin "a") (pinfunction "a_a") (pintype "passive"))
      (node (ref "Q2") (pin "1") (pinfunction "1_1") (pintype "passive"))
      (node (ref "R33") (pin "2") (pinfunction "2_2") (pintype "passive"))
      (node (ref "R41") (pin "1") (pinfunction "1_1") (pintype "passive"))
    )
    (net (code "30") (name "Net-(D10-Pada)") (class "Default")
      (node (ref "D10") (pin "a") (pinfunction "a_a") (pintype "passive"))
      (node (ref "Q3") (pin "1") (pinfunction "1_1") (pintype "passive"))
      (node (ref "R34") (pin "2") (pinfunction "2_2") (pintype "passive"))
      (node (ref "R42") (pin "1") (pinfunction "1_1") (pintype "passive"))
    )
    (net (code "31") (name "Net-(D11-Pada)") (class "Default")
      (node (ref "D11") (pin "a") (pinfunction "a_a") (pintype "passive"))
      (node (ref "Q4") (pin "1") (pinfunction "1_1") (pintype "passive"))
      (node (ref "R35") (pin "2") (pinfunction "2_2") (pintype "passive"))
      (node (ref "R43") (pin "1") (pinfunction "1_1") (pintype "passive"))
    )
    (net (code "32") (name "Net-(D12-Pada)") (class "Default")
      (node (ref "D12") (pin "a") (pinfunction "a_a") (pintype "passive"))
      (node (ref "Q5") (pin "1") (pinfunction "1_1") (pintype "passive"))
      (node (ref "R36") (pin "2") (pinfunction "2_2") (pintype "passive"))
      (node (ref "R44") (pin "1") (pinfunction "1_1") (pintype "passive"))
    )
    (net (code "33") (name "Net-(D13-Pad1)") (class "Default")
      (node (ref "D13") (pin "1") (pinfunction "1_1") (pintype "passive"))
      (node (ref "D15") (pin "2") (pinfunction "2_2") (pintype "passive"))
      (node (ref "T1") (pin "1") (pinfunction "1_1") (pintype "passive"))
    )
    (net (code "34") (name "Net-(D17-Pada)") (class "Default")
      (node (ref "D17") (pin "a") (pinfunction "a_a") (pintype "passive"))
      (node (ref "Q8") (pin "1") (pinfunction "1_1") (pintype "passive"))
      (node (ref "R47") (pin "2") (pinfunction "2_2") (pintype "passive"))
      (node (ref "R53") (pin "1") (pinfunction "1_1") (pintype "passive"))
    )
    (net (code "35") (name "Net-(D18-Pada)") (class "Default")
      (node (ref "D18") (pin "a") (pinfunction "a_a") (pintype "passive"))
      (node (ref "Q9") (pin "1") (pinfunction "1_1") (pintype "passive"))
      (node (ref "R48") (pin "2") (pinfunction "2_2") (pintype "passive"))
      (node (ref "R54") (pin "1") (pinfunction "1_1") (pintype "passive"))
    )
    (net (code "36") (name "Net-(D19-Pada)") (class "Default")
      (node (ref "D19") (pin "a") (pinfunction "a_a") (pintype "passive"))
      (node (ref "Q10") (pin "1") (pinfunction "1_1") (pintype "passive"))
      (node (ref "R49") (pin "2") (pinfunction "2_2") (pintype "passive"))
      (node (ref "R55") (pin "1") (pinfunction "1_1") (pintype "passive"))
    )
    (net (code "37") (name "Net-(D20-Pada)") (class "Default")
      (node (ref "D20") (pin "a") (pinfunction "a_a") (pintype "passive"))
      (node (ref "Q11") (pin "1") (pinfunction "1_1") (pintype "passive"))
      (node (ref "R50") (pin "2") (pinfunction "2_2") (pintype "passive"))
      (node (ref "R56") (pin "1") (pinfunction "1_1") (pintype "passive"))
    )
    (net (code "38") (name "Net-(D21-Pada)") (class "Default")
      (node (ref "D21") (pin "a") (pinfunction "a_a") (pintype "passive"))
      (node (ref "R57") (pin "1") (pinfunction "1_1") (pintype "passive"))
    )
    (net (code "39") (name "Net-(D22-Pada)") (class "Default")
      (node (ref "D22") (pin "a") (pinfunction "a_a") (pintype "passive"))
      (node (ref "R58") (pin "1") (pinfunction "1_1") (pintype "passive"))
    )
    (net (code "40") (name "Net-(IC2-CATHODE)") (class "Default")
      (node (ref "IC2") (pin "1") (pinfunction "CATHODE_1") (pintype "passive"))
      (node (ref "R63") (pin "1") (pinfunction "1_1") (pintype "passive"))
    )
    (net (code "41") (name "Net-(IC2-REF)") (class "Default")
      (node (ref "C66") (pin "2") (pinfunction "2_2") (pintype "passive"))
      (node (ref "IC2") (pin "2") (pinfunction "REF_2") (pintype "passive"))
      (node (ref "R68") (pin "1") (pinfunction "1_1") (pintype "passive"))
      (node (ref "R70") (pin "2") (pinfunction "2_2") (pintype "passive"))
      (node (ref "R71") (pin "2") (pinfunction "2_2") (pintype "passive"))
    )
    (net (code "42") (name "Net-(IC3-CATHODE)") (class "Default")
      (node (ref "IC3") (pin "2") (pinfunction "CATHODE_2") (pintype "passive"))
      (node (ref "R63") (pin "2") (pinfunction "2_2") (pintype "passive"))
      (node (ref "R69") (pin "2") (pinfunction "2_2") (pintype "passive"))
    )
    (net (code "43") (name "Net-(IC3-COLLECTOR)") (class "Default")
      (node (ref "IC3") (pin "4") (pinfunction "COLLECTOR_4") (pintype "passive"))
      (node (ref "R67") (pin "2") (pinfunction "2_2") (pintype "passive"))
    )
    (net (code "44") (name "Net-(L6-Pad1)") (class "Default")
      (node (ref "L6") (pin "1") (pinfunction "1_1") (pintype "passive"))
      (node (ref "X2") (pin "4") (pinfunction "4_4") (pintype "passive"))
    )
    (net (code "45") (name "Net-(L6-Pad2)") (class "Default")
      (node (ref "L6") (pin "2") (pinfunction "2_2") (pintype "passive"))
      (node (ref "T1") (pin "2") (pinfunction "2_2") (pintype "passive"))
    )
    (net (code "46") (name "Net-(Q6-Pad1)") (class "Default")
      (node (ref "Q6") (pin "1") (pinfunction "1_1") (pintype "passive"))
      (node (ref "R2") (pin "2") (pinfunction "2_2") (pintype "passive"))
      (node (ref "R37") (pin "2") (pinfunction "2_2") (pintype "passive"))
      (node (ref "R39") (pin "2") (pinfunction "2_2") (pintype "passive"))
    )
    (net (code "47") (name "Net-(Q7-Pad1)") (class "Default")
      (node (ref "Q7") (pin "1") (pinfunction "1_1") (pintype "passive"))
      (node (ref "R38") (pin "2") (pinfunction "2_2") (pintype "passive"))
      (node (ref "R40") (pin "2") (pinfunction "2_2") (pintype "passive"))
      (node (ref "R75") (pin "2") (pinfunction "2_2") (pintype "passive"))
    )
    (net (code "48") (name "Net-(Q12-Pad1)") (class "Default")
      (node (ref "Q12") (pin "1") (pinfunction "1_1") (pintype "passive"))
      (node (ref "R51") (pin "2") (pinfunction "2_2") (pintype "passive"))
      (node (ref "R58") (pin "2") (pinfunction "2_2") (pintype "passive"))
      (node (ref "R76") (pin "2") (pinfunction "2_2") (pintype "passive"))
    )
    (net (code "49") (name "Net-(Q13-Pad1)") (class "Default")
      (node (ref "Q13") (pin "1") (pinfunction "1_1") (pintype "passive"))
      (node (ref "R52") (pin "2") (pinfunction "2_2") (pintype "passive"))
      (node (ref "R57") (pin "2") (pinfunction "2_2") (pintype "passive"))
      (node (ref "R77") (pin "2") (pinfunction "2_2") (pintype "passive"))
    )
    (net (code "50") (name "Net-(Q14-B)") (class "Default")
      (node (ref "Q14") (pin "1") (pinfunction "B_1") (pintype "passive"))
      (node (ref "R66") (pin "2") (pinfunction "2_2") (pintype "passive"))
    )
    (net (code "51") (name "Net-(R26-CW)") (class "Default")
      (node (ref "C28") (pin "2") (pinfunction "2_2") (pintype "passive"))
      (node (ref "R22") (pin "1") (pinfunction "1_1") (pintype "passive"))
      (node (ref "R26") (pin "2") (pinfunction "WIPER_2") (pintype "passive"))
      (node (ref "R26") (pin "3") (pinfunction "CW_3") (pintype "passive"))
      (node (ref "R29") (pin "2") (pinfunction "2_2") (pintype "passive"))
      (node (ref "eg002") (pin "15") (pinfunction "VFB_15") (pintype "passive"))
    )
    (net (code "52") (name "Net-(R30-Pad1)") (class "Default")
      (node (ref "R30") (pin "1") (pinfunction "1_1") (pintype "passive"))
      (node (ref "R45") (pin "2") (pinfunction "2_2") (pintype "passive"))
    )
    (net (code "53") (name "Net-(R30-Pad2)") (class "Default")
      (node (ref "R30") (pin "2") (pinfunction "2_2") (pintype "passive"))
      (node (ref "R73") (pin "1") (pinfunction "1_1") (pintype "passive"))
    )
    (net (code "54") (name "Net-(R64-Pad1)") (class "Default")
      (node (ref "R64") (pin "1") (pinfunction "1_1") (pintype "passive"))
      (node (ref "R68") (pin "2") (pinfunction "2_2") (pintype "passive"))
    )
    (net (code "55") (name "Net-(U4-IFB)") (class "Default")
      (node (ref "D5") (pin "k") (pinfunction "k_k") (pintype "passive"))
      (node (ref "D6") (pin "k") (pinfunction "k_k") (pintype "passive"))
      (node (ref "R28") (pin "1") (pinfunction "1_1") (pintype "passive"))
      (node (ref "U4") (pin "14") (pinfunction "IFB_14") (pintype "passive"))
    )
    (net (code "56") (name "Net-(U4-Temp)") (class "Default")
      (node (ref "R32") (pin "2") (pinfunction "2_2") (pintype "passive"))
      (node (ref "U4") (pin "1") (pinfunction "Temp_1") (pintype "passive"))
    )
    (net (code "57") (name "Net-(U7-VIOUT)") (class "Default")
      (node (ref "R74") (pin "1") (pinfunction "1_1") (pintype "passive"))
      (node (ref "U7") (pin "3") (pinfunction "VIOUT_3") (pintype "passive"))
    )
    (net (code "58") (name "Net-(eg002-TFB)") (class "Default")
      (node (ref "C33") (pin "1") (pinfunction "1_1") (pintype "passive"))
      (node (ref "R27") (pin "2") (pinfunction "2_2") (pintype "passive"))
      (node (ref "eg002") (pin "16") (pinfunction "TFB_16") (pintype "passive"))
    )
    (net (code "59") (name "T1") (class "Default")
      (node (ref "Q2") (pin "2") (pinfunction "2_2") (pintype "passive"))
      (node (ref "Q3") (pin "2") (pinfunction "2_2") (pintype "passive"))
      (node (ref "Q8") (pin "3") (pinfunction "3_3") (pintype "passive"))
      (node (ref "Q9") (pin "3") (pinfunction "3_3") (pintype "passive"))
      (node (ref "R41") (pin "2") (pinfunction "2_2") (pintype "passive"))
      (node (ref "R42") (pin "2") (pinfunction "2_2") (pintype "passive"))
      (node (ref "T1") (pin "3") (pinfunction "3_3") (pintype "passive"))
      (node (ref "U4") (pin "12") (pinfunction "VS2_12") (pintype "passive"))
    )
    (net (code "60") (name "T2") (class "Default")
      (node (ref "Q10") (pin "3") (pinfunction "3_3") (pintype "passive"))
      (node (ref "Q11") (pin "3") (pinfunction "3_3") (pintype "passive"))
      (node (ref "Q4") (pin "2") (pinfunction "2_2") (pintype "passive"))
      (node (ref "Q5") (pin "2") (pinfunction "2_2") (pintype "passive"))
      (node (ref "R43") (pin "2") (pinfunction "2_2") (pintype "passive"))
      (node (ref "R44") (pin "2") (pinfunction "2_2") (pintype "passive"))
      (node (ref "T1") (pin "4") (pinfunction "4_4") (pintype "passive"))
      (node (ref "U4") (pin "9") (pinfunction "VS1_9") (pintype "passive"))
    )
    (net (code "61") (name "VFB") (class "Default")
      (node (ref "C60") (pin "1") (pinfunction "1_1") (pintype "passive"))
      (node (ref "IC3") (pin "3") (pinfunction "EMITTER_3") (pintype "passive"))
      (node (ref "R65") (pin "1") (pinfunction "1_1") (pintype "passive"))
      (node (ref "U4") (pin "5") (pinfunction "VFB_5") (pintype "passive"))
    )
    (net (code "62") (name "VFBAC") (class "Default")
      (node (ref "C59") (pin "2") (pinfunction "2_2") (pintype "passive"))
      (node (ref "L7") (pin "3") (pinfunction "3_3") (pintype "passive"))
      (node (ref "R29") (pin "1") (pinfunction "1_1") (pintype "passive"))
    )
    (net (code "63") (name "VS12") (class "Default")
      (node (ref "L7") (pin "1") (pinfunction "1_1") (pintype "passive"))
      (node (ref "Q13") (pin "2") (pinfunction "2_2") (pintype "passive"))
      (node (ref "Q7") (pin "3") (pinfunction "3_3") (pintype "passive"))
      (node (ref "R75") (pin "1") (pinfunction "1_1") (pintype "passive"))
      (node (ref "eg002") (pin "5") (pinfunction "VSI_5") (pintype "passive"))
    )
    (net (code "64") (name "VS22") (class "Default")
      (node (ref "L7") (pin "2") (pinfunction "2_2") (pintype "passive"))
      (node (ref "Q12") (pin "2") (pinfunction "2_2") (pintype "passive"))
      (node (ref "Q6") (pin "3") (pinfunction "3_3") (pintype "passive"))
      (node (ref "R2") (pin "1") (pinfunction "1_1") (pintype "passive"))
      (node (ref "eg002") (pin "9") (pinfunction "VS2_9") (pintype "passive"))
    )
    (net (code "65") (name "beep") (class "Default")
      (node (ref "Con7") (pin "2") (pinfunction "pin2_2") (pintype "passive"))
      (node (ref "U4") (pin "2") (pinfunction "Beep_2") (pintype "passive"))
    )
    (net (code "66") (name "fan") (class "Default")
      (node (ref "R66") (pin "1") (pinfunction "1_1") (pintype "passive"))
      (node (ref "U4") (pin "4") (pinfunction "FAN_4") (pintype "passive"))
    )
    (net (code "67") (name "unconnected-(U6-NC-Pad2)") (class "Default")
      (node (ref "U6") (pin "2") (pinfunction "NC_2") (pintype "passive"))
    )
    (net (code "68") (name "unconnected-(eg002-FAN-Pad17)") (class "Default")
      (node (ref "eg002") (pin "17") (pinfunction "FAN_17") (pintype "passive+no_connect"))
    )
  )
)
